# 5V_AC-DC.net
KiCad netlist of a schematic drawn in EAGLE
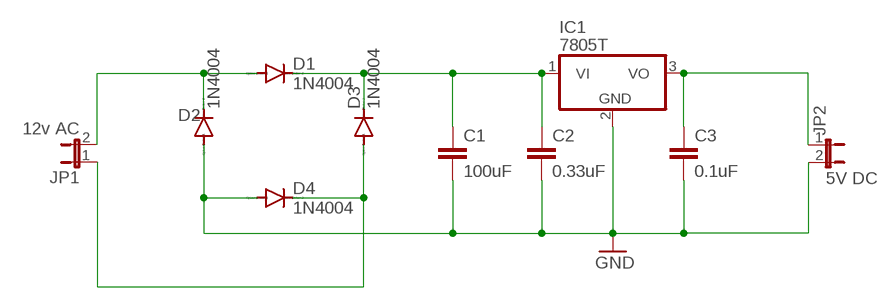
[diagram p0: schematic, sheet 1]

(export (version "E")
  (design (tool "Eeschema 10.0.6"))
  (components
    (comp (ref "C1")
      (value "100uF")
      (footprint "eagle-import:C2.5-3")
      (libsource (lib "eagle-import") (part "C2,5-3"))
    )
    (comp (ref "C2")
      (value "0.33uF")
      (footprint "eagle-import:C2.5-3")
      (libsource (lib "eagle-import") (part "C2,5-3"))
    )
    (comp (ref "C3")
      (value "0.1uF")
      (footprint "eagle-import:C2.5-3")
      (libsource (lib "eagle-import") (part "C2,5-3"))
    )
    (comp (ref "D1")
      (value "1N4004")
      (footprint "eagle-import:DO41-10")
      (libsource (lib "eagle-import") (part "1N4004"))
    )
    (comp (ref "D2")
      (value "1N4004")
      (footprint "eagle-import:DO41-10")
      (libsource (lib "eagle-import") (part "1N4004"))
    )
    (comp (ref "D3")
      (value "1N4004")
      (footprint "eagle-import:DO41-10")
      (libsource (lib "eagle-import") (part "1N4004"))
    )
    (comp (ref "D4")
      (value "1N4004")
      (footprint "eagle-import:DO41-10")
      (libsource (lib "eagle-import") (part "1N4004"))
    )
    (comp (ref "IC1")
      (value "7805T")
      (footprint "eagle-import:TO220H")
      (libsource (lib "eagle-import") (part "78T05"))
    )
    (comp (ref "JP1")
      (value "12v AC")
      (footprint "eagle-import:JP1")
      (libsource (lib "eagle-import") (part "JP1E"))
    )
    (comp (ref "JP2")
      (value "5V DC")
      (footprint "eagle-import:JP1")
      (libsource (lib "eagle-import") (part "JP1E"))
    )
  )
  (nets
    (net (code "1") (name "GND") (class "Default")
      (node (ref "C1") (pin "2") (pinfunction "2_2") (pintype "passive"))
      (node (ref "C2") (pin "2") (pinfunction "2_2") (pintype "passive"))
      (node (ref "C3") (pin "2") (pinfunction "2_2") (pintype "passive"))
      (node (ref "D2") (pin "A") (pinfunction "A_A") (pintype "passive"))
      (node (ref "D4") (pin "A") (pinfunction "A_A") (pintype "passive"))
      (node (ref "IC1") (pin "2") (pinfunction "GND_2") (pintype "passive"))
      (node (ref "JP2") (pin "2") (pinfunction "2_2") (pintype "passive"))
    )
    (net (code "2") (name "Net-(D1-PadA)") (class "Default")
      (node (ref "D1") (pin "A") (pinfunction "A_A") (pintype "passive"))
      (node (ref "D2") (pin "C") (pinfunction "C_C") (pintype "passive"))
      (node (ref "JP1") (pin "2") (pinfunction "2_2") (pintype "passive"))
    )
    (net (code "3") (name "Net-(D3-PadA)") (class "Default")
      (node (ref "D3") (pin "A") (pinfunction "A_A") (pintype "passive"))
      (node (ref "D4") (pin "C") (pinfunction "C_C") (pintype "passive"))
      (node (ref "JP1") (pin "1") (pinfunction "1_1") (pintype "passive"))
    )
    (net (code "4") (name "Net-(IC1-VI)") (class "Default")
      (node (ref "C1") (pin "1") (pinfunction "1_1") (pintype "passive"))
      (node (ref "C2") (pin "1") (pinfunction "1_1") (pintype "passive"))
      (node (ref "D1") (pin "C") (pinfunction "C_C") (pintype "passive"))
      (node (ref "D3") (pin "C") (pinfunction "C_C") (pintype "passive"))
      (node (ref "IC1") (pin "1") (pinfunction "VI_1") (pintype "input"))
    )
    (net (code "5") (name "Net-(IC1-VO)") (class "Default")
      (node (ref "C3") (pin "1") (pinfunction "1_1") (pintype "passive"))
      (node (ref "IC1") (pin "3") (pinfunction "VO_3") (pintype "passive"))
      (node (ref "JP2") (pin "1") (pinfunction "1_1") (pintype "passive"))
    )
  )
)
